# temp_press_v2.net
KiCad netlist of a schematic drawn in EAGLE
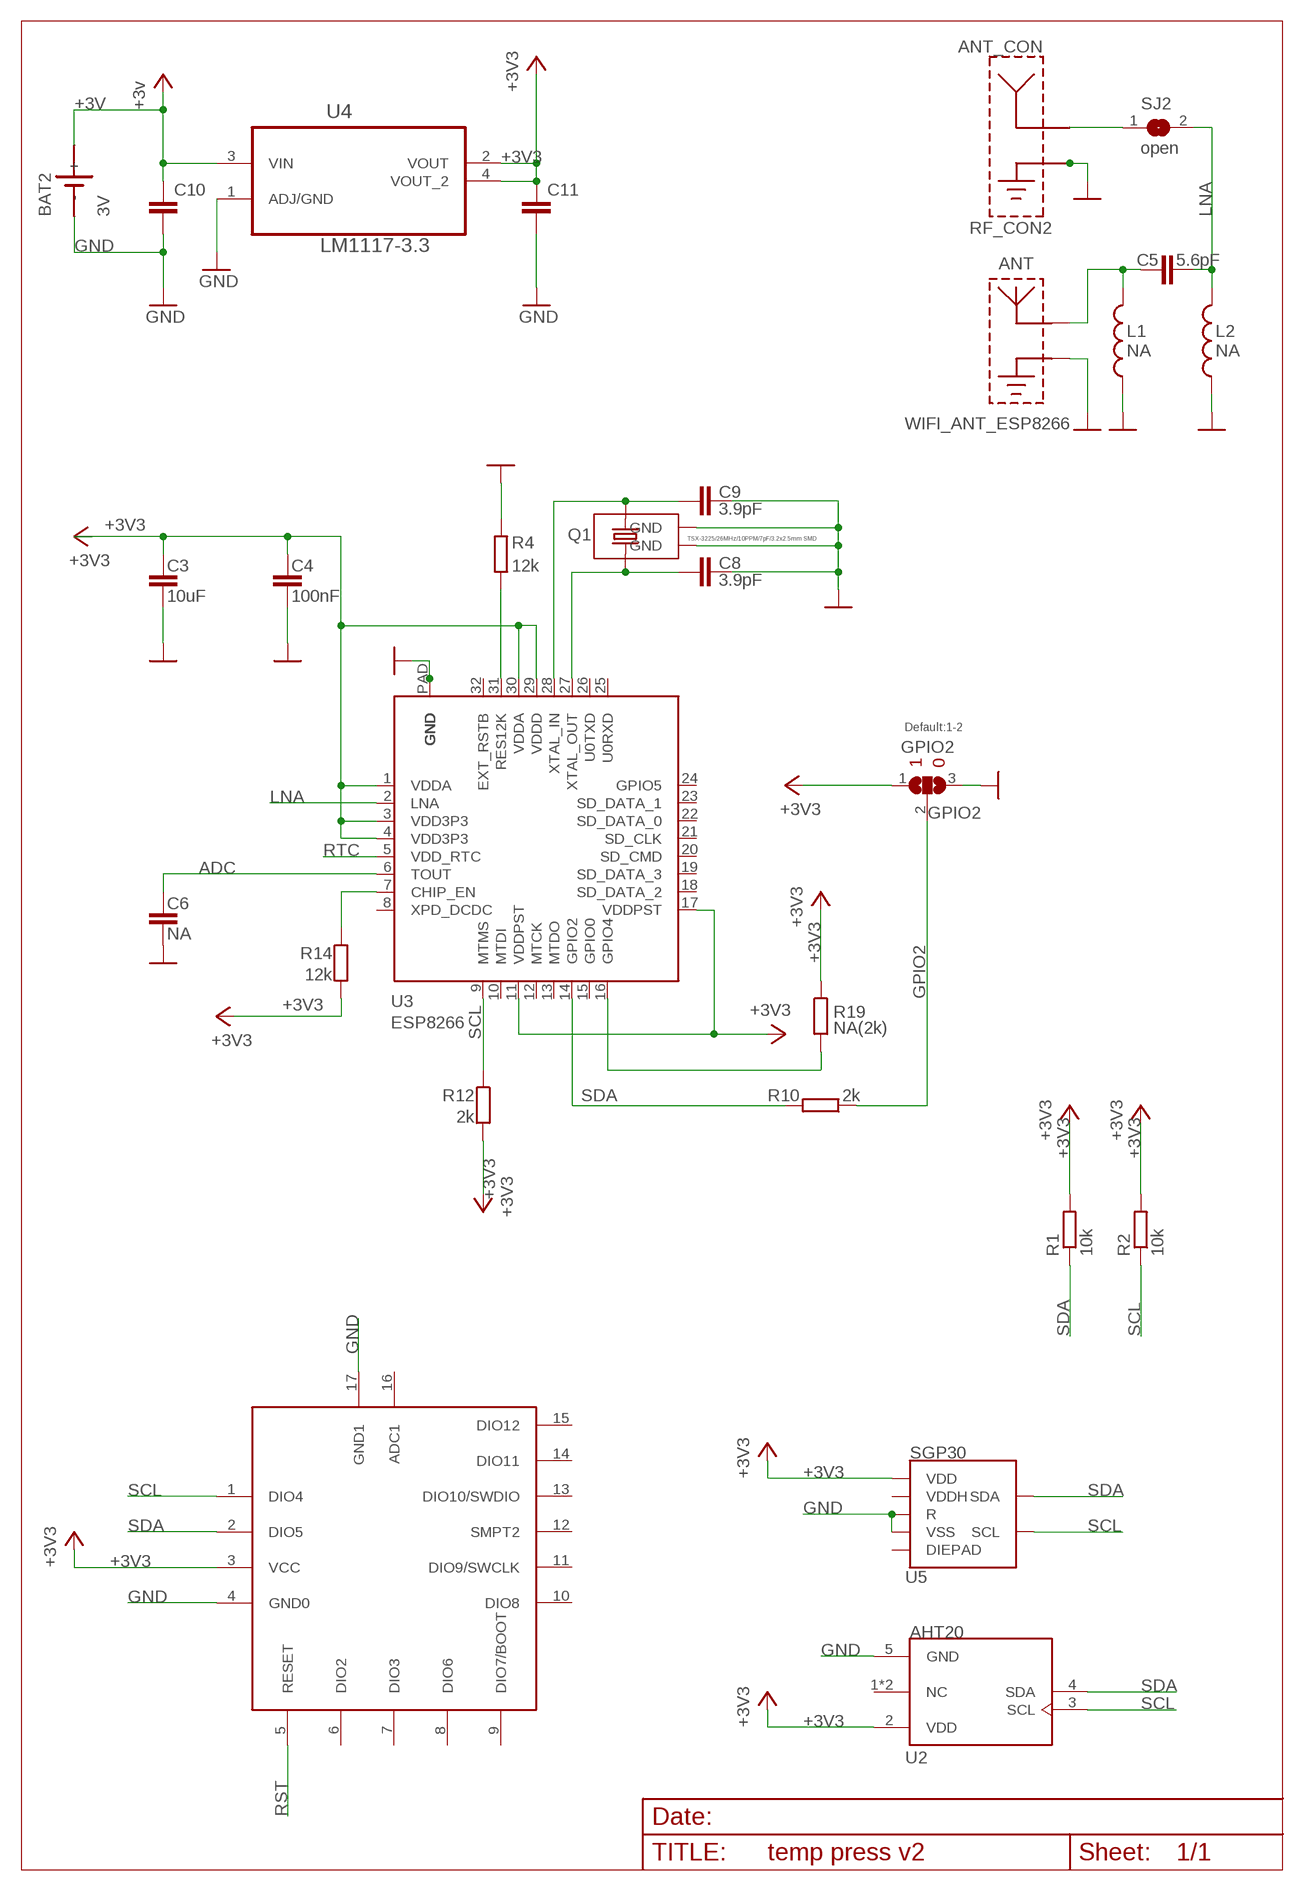
[diagram p0: schematic, sheet 1]

(export (version "E")
  (design (tool "Eeschema 10.0.6"))
  (components
    (comp (ref "ANT")
      (value "WIFI_ANT_ESP8266")
      (footprint "eagle-import:ESP8266_ANT")
      (libsource (lib "eagle-import") (part "WIFI_ANT_ESP8266"))
    )
    (comp (ref "ANT_CON")
      (value "RF_CON2")
      (footprint "eagle-import:RF_CONNECTOR_I-PEX_NO_CREAM")
      (libsource (lib "eagle-import") (part "RF_CON2"))
    )
    (comp (ref "BAT2")
      (value "3V")
      (footprint "eagle-import:SN2032")
      (libsource (lib "eagle-import") (part "SN2032"))
    )
    (comp (ref "C3")
      (value "10uF")
      (footprint "eagle-import:C0603_DWS")
      (libsource (lib "eagle-import") (part "C-EUC0603_DWS"))
    )
    (comp (ref "C4")
      (value "100nF")
      (footprint "eagle-import:C0402_TI")
      (libsource (lib "eagle-import") (part "C-EUC0402_TI"))
    )
    (comp (ref "C5")
      (value "5.6pF")
      (footprint "eagle-import:C0402_TI")
      (libsource (lib "eagle-import") (part "C-EUC0402_TI"))
    )
    (comp (ref "C6")
      (value "NA")
      (footprint "eagle-import:C0402_TI")
      (libsource (lib "eagle-import") (part "C-EUC0402_TI"))
    )
    (comp (ref "C8")
      (value "3.9pF")
      (footprint "eagle-import:C0402_TI")
      (libsource (lib "eagle-import") (part "C-EUC0402_TI"))
    )
    (comp (ref "C9")
      (value "3.9pF")
      (footprint "eagle-import:C0402_TI")
      (libsource (lib "eagle-import") (part "C-EUC0402_TI"))
    )
    (comp (ref "C10")
      (value "47u")
      (footprint "eagle-import:C1206")
      (libsource (lib "eagle-import") (part "rcl_334_C-EUC1206"))
    )
    (comp (ref "C11")
      (value "10u")
      (footprint "eagle-import:C1206")
      (libsource (lib "eagle-import") (part "rcl_334_C-EUC1206"))
    )
    (comp (ref "GPIO2")
      (value "Default:1-2")
      (footprint "eagle-import:SJ_2_SMALLER")
      (libsource (lib "eagle-import") (part "SJ2W4"))
    )
    (comp (ref "L1")
      (value "NA")
      (footprint "eagle-import:L0402_TI")
      (libsource (lib "eagle-import") (part "L-USL0402_TI"))
    )
    (comp (ref "L2")
      (value "NA")
      (footprint "eagle-import:L0402_TI")
      (libsource (lib "eagle-import") (part "L-USL0402_TI"))
    )
    (comp (ref "Q1")
      (value "TSX-3225/26MHz/10PPM/7pF/3.2x2.5mm SMD")
      (footprint "eagle-import:NX3225SA")
      (libsource (lib "eagle-import") (part "SMALL_SMD_CRYSTAL_1"))
    )
    (comp (ref "R1")
      (value "10k")
      (footprint "eagle-import:R0402")
      (libsource (lib "eagle-import") (part "rcl_334_R-EU_R0402"))
    )
    (comp (ref "R2")
      (value "10k")
      (footprint "eagle-import:R0402")
      (libsource (lib "eagle-import") (part "rcl_334_R-EU_R0402"))
    )
    (comp (ref "R4")
      (value "12k")
      (footprint "eagle-import:R0402_TI")
      (libsource (lib "eagle-import") (part "R-EU_R0402_TI"))
    )
    (comp (ref "R10")
      (value "2k")
      (footprint "eagle-import:R0402_TI")
      (libsource (lib "eagle-import") (part "R-EU_R0402_TI"))
    )
    (comp (ref "R12")
      (value "2k")
      (footprint "eagle-import:R0402_TI")
      (libsource (lib "eagle-import") (part "R-EU_R0402_TI"))
    )
    (comp (ref "R14")
      (value "12k")
      (footprint "eagle-import:R0402_TI")
      (libsource (lib "eagle-import") (part "R-EU_R0402_TI"))
    )
    (comp (ref "R19")
      (value "NA(2k)")
      (footprint "eagle-import:R0402_TI")
      (libsource (lib "eagle-import") (part "R-EU_R0402_TI"))
    )
    (comp (ref "SJ2")
      (value "open")
      (footprint "eagle-import:SJ_1_SMALLER")
      (libsource (lib "eagle-import") (part "SJSJ_SMALLER"))
    )
    (comp (ref "U$1")
      (value "BLUENRG-234BLEMODULE")
      (footprint "eagle-import:BLUENRG-234BLEMODULE")
      (libsource (lib "eagle-import") (part "BLUENRG-234BLEMODULE"))
    )
    (comp (ref "U2")
      (value "AHT20")
      (footprint "eagle-import:PSON100P300X300X110-6N")
      (fields (field (name "MF") "Asair"))
      (libsource (lib "eagle-import") (part "AHT20"))
    )
    (comp (ref "U3")
      (value "ESP8266")
      (footprint "eagle-import:QFN32_PAD")
      (libsource (lib "eagle-import") (part "ESP8266"))
    )
    (comp (ref "U4")
      (value "LM1117-3.3")
      (footprint "eagle-import:SOT230")
      (fields (field (name "MF") "Texas Instruments"))
      (libsource (lib "eagle-import") (part "LM1117-3.3"))
    )
    (comp (ref "U5")
      (value "SGP30")
      (footprint "eagle-import:SGP30")
      (fields (field (name "MF") "Sensirion AG"))
      (libsource (lib "eagle-import") (part "SGP30"))
    )
  )
  (nets
    (net (code "1") (name "+3V3") (class "Default")
      (node (ref "C11") (pin "1") (pinfunction "1_1") (pintype "passive"))
      (node (ref "C3") (pin "1") (pinfunction "1_1") (pintype "passive"))
      (node (ref "C4") (pin "1") (pinfunction "1_1") (pintype "passive"))
      (node (ref "GPIO2") (pin "1") (pinfunction "1_1") (pintype "passive"))
      (node (ref "R1") (pin "2") (pinfunction "2_2") (pintype "passive"))
      (node (ref "R12") (pin "2") (pinfunction "2_2") (pintype "passive"))
      (node (ref "R14") (pin "2") (pinfunction "2_2") (pintype "passive"))
      (node (ref "R19") (pin "1") (pinfunction "1_1") (pintype "passive"))
      (node (ref "R2") (pin "2") (pinfunction "2_2") (pintype "passive"))
      (node (ref "U$1") (pin "3") (pinfunction "VCC_3") (pintype "bidirectional"))
      (node (ref "U2") (pin "2") (pinfunction "VDD_2") (pintype "power_in"))
      (node (ref "U3") (pin "1") (pinfunction "VDDA_1") (pintype "bidirectional"))
      (node (ref "U3") (pin "11") (pinfunction "VDDPST_11") (pintype "bidirectional"))
      (node (ref "U3") (pin "17") (pinfunction "VDDPST_17") (pintype "bidirectional"))
      (node (ref "U3") (pin "29") (pinfunction "VDDD_29") (pintype "bidirectional"))
      (node (ref "U3") (pin "3") (pinfunction "VDD3P3_3") (pintype "bidirectional"))
      (node (ref "U3") (pin "30") (pinfunction "VDDA_30") (pintype "bidirectional"))
      (node (ref "U3") (pin "4") (pinfunction "VDD3P3_4") (pintype "bidirectional"))
      (node (ref "U4") (pin "2") (pinfunction "VOUT_2") (pintype "output"))
      (node (ref "U4") (pin "4") (pinfunction "VOUT_2_4") (pintype "output"))
      (node (ref "U5") (pin "1") (pinfunction "VDD_1") (pintype "bidirectional"))
    )
    (net (code "2") (name "+3v") (class "Default")
      (node (ref "BAT2") (pin "+") (pinfunction "+_+") (pintype "passive"))
      (node (ref "C10") (pin "1") (pinfunction "1_1") (pintype "passive"))
      (node (ref "U4") (pin "3") (pinfunction "VIN_3") (pintype "input"))
    )
    (net (code "3") (name "/ADC") (class "Default")
      (node (ref "C6") (pin "1") (pinfunction "1_1") (pintype "passive"))
      (node (ref "U3") (pin "6") (pinfunction "TOUT_6") (pintype "bidirectional"))
    )
    (net (code "4") (name "/GPIO2") (class "Default")
      (node (ref "GPIO2") (pin "2") (pinfunction "2_2") (pintype "passive"))
      (node (ref "R10") (pin "1") (pinfunction "1_1") (pintype "passive"))
    )
    (net (code "5") (name "/LNA") (class "Default")
      (node (ref "C5") (pin "2") (pinfunction "2_2") (pintype "passive"))
      (node (ref "L2") (pin "2") (pinfunction "2_2") (pintype "passive"))
      (node (ref "SJ2") (pin "2") (pinfunction "2_2") (pintype "passive"))
      (node (ref "U3") (pin "2") (pinfunction "LNA_2") (pintype "bidirectional"))
    )
    (net (code "6") (name "/RST") (class "Default")
      (node (ref "U$1") (pin "5") (pinfunction "RESET_5") (pintype "bidirectional"))
    )
    (net (code "7") (name "/RTC") (class "Default")
      (node (ref "U3") (pin "5") (pinfunction "VDD_RTC_5") (pintype "bidirectional"))
    )
    (net (code "8") (name "/SCL") (class "Default")
      (node (ref "R12") (pin "1") (pinfunction "1_1") (pintype "passive"))
      (node (ref "R2") (pin "1") (pinfunction "1_1") (pintype "passive"))
      (node (ref "U$1") (pin "1") (pinfunction "DIO4_1") (pintype "bidirectional"))
      (node (ref "U2") (pin "3") (pinfunction "SCL_3") (pintype "input"))
      (node (ref "U3") (pin "9") (pinfunction "MTMS_9") (pintype "bidirectional"))
      (node (ref "U5") (pin "6") (pinfunction "SCL_6") (pintype "bidirectional"))
    )
    (net (code "9") (name "/SDA") (class "Default")
      (node (ref "R1") (pin "1") (pinfunction "1_1") (pintype "passive"))
      (node (ref "R10") (pin "2") (pinfunction "2_2") (pintype "passive"))
      (node (ref "U$1") (pin "2") (pinfunction "DIO5_2") (pintype "bidirectional"))
      (node (ref "U2") (pin "4") (pinfunction "SDA_4") (pintype "bidirectional"))
      (node (ref "U3") (pin "14") (pinfunction "GPIO2_14") (pintype "bidirectional"))
      (node (ref "U5") (pin "3") (pinfunction "SDA_3") (pintype "bidirectional"))
    )
    (net (code "10") (name "GND") (class "Default")
      (node (ref "ANT") (pin "GND") (pinfunction "GND_GND") (pintype "input"))
      (node (ref "ANT_CON") (pin "1") (pinfunction "GND_1_1") (pintype "input"))
      (node (ref "ANT_CON") (pin "2") (pinfunction "GND_2_2") (pintype "input"))
      (node (ref "BAT2") (pin "-") (pinfunction "-_-") (pintype "passive"))
      (node (ref "C10") (pin "2") (pinfunction "2_2") (pintype "passive"))
      (node (ref "C11") (pin "2") (pinfunction "2_2") (pintype "passive"))
      (node (ref "C3") (pin "2") (pinfunction "2_2") (pintype "passive"))
      (node (ref "C4") (pin "2") (pinfunction "2_2") (pintype "passive"))
      (node (ref "C6") (pin "2") (pinfunction "2_2") (pintype "passive"))
      (node (ref "C8") (pin "1") (pinfunction "1_1") (pintype "passive"))
      (node (ref "C9") (pin "1") (pinfunction "1_1") (pintype "passive"))
      (node (ref "GPIO2") (pin "3") (pinfunction "3_3") (pintype "passive"))
      (node (ref "L1") (pin "1") (pinfunction "1_1") (pintype "passive"))
      (node (ref "L2") (pin "1") (pinfunction "1_1") (pintype "passive"))
      (node (ref "Q1") (pin "NC_1") (pinfunction "GND_NC_1") (pintype "power_in"))
      (node (ref "Q1") (pin "NC_2") (pinfunction "GND_NC_2") (pintype "power_in"))
      (node (ref "R4") (pin "2") (pinfunction "2_2") (pintype "passive"))
      (node (ref "U$1") (pin "17") (pinfunction "GND1_17") (pintype "bidirectional"))
      (node (ref "U$1") (pin "4") (pinfunction "GND0_4") (pintype "bidirectional"))
      (node (ref "U2") (pin "5") (pinfunction "GND_5") (pintype "power_in"))
      (node (ref "U3") (pin "P$1") (pinfunction "GND_P$1") (pintype "bidirectional"))
      (node (ref "U3") (pin "P$2") (pinfunction "GND_P$2") (pintype "bidirectional"))
      (node (ref "U3") (pin "P$3") (pinfunction "GND_P$3") (pintype "bidirectional"))
      (node (ref "U3") (pin "P$4") (pinfunction "GND_P$4") (pintype "bidirectional"))
      (node (ref "U3") (pin "P$5") (pinfunction "GND_P$5") (pintype "bidirectional"))
      (node (ref "U3") (pin "P$6") (pinfunction "GND_P$6") (pintype "bidirectional"))
      (node (ref "U3") (pin "P$7") (pinfunction "GND_P$7") (pintype "bidirectional"))
      (node (ref "U3") (pin "P$8") (pinfunction "GND_P$8") (pintype "bidirectional"))
      (node (ref "U3") (pin "P$9") (pinfunction "GND_P$9") (pintype "bidirectional"))
      (node (ref "U3") (pin "PAD") (pinfunction "GND_PAD") (pintype "bidirectional"))
      (node (ref "U4") (pin "1") (pinfunction "ADJ/GND_1") (pintype "passive"))
      (node (ref "U5") (pin "2") (pinfunction "VSS_2") (pintype "bidirectional"))
      (node (ref "U5") (pin "4") (pinfunction "R_4") (pintype "bidirectional"))
    )
    (net (code "11") (name "Net-(ANT-PadANT)") (class "Default")
      (node (ref "ANT") (pin "ANT") (pinfunction "ANT_ANT") (pintype "input"))
      (node (ref "C5") (pin "1") (pinfunction "1_1") (pintype "passive"))
      (node (ref "L1") (pin "2") (pinfunction "2_2") (pintype "passive"))
    )
    (net (code "12") (name "Net-(ANT_CON-PadANT)") (class "Default")
      (node (ref "ANT_CON") (pin "ANT") (pinfunction "ANT_ANT") (pintype "power_in"))
      (node (ref "SJ2") (pin "1") (pinfunction "1_1") (pintype "passive"))
    )
    (net (code "13") (name "Net-(U3-CHIP_EN)") (class "Default")
      (node (ref "R14") (pin "1") (pinfunction "1_1") (pintype "passive"))
      (node (ref "U3") (pin "7") (pinfunction "CHIP_EN_7") (pintype "bidirectional"))
    )
    (net (code "14") (name "Net-(U3-GPIO4)") (class "Default")
      (node (ref "R19") (pin "2") (pinfunction "2_2") (pintype "passive"))
      (node (ref "U3") (pin "16") (pinfunction "GPIO4_16") (pintype "bidirectional"))
    )
    (net (code "15") (name "Net-(U3-RES12K)") (class "Default")
      (node (ref "R4") (pin "1") (pinfunction "1_1") (pintype "passive"))
      (node (ref "U3") (pin "31") (pinfunction "RES12K_31") (pintype "bidirectional"))
    )
    (net (code "16") (name "Net-(U3-XTAL_IN)") (class "Default")
      (node (ref "C9") (pin "2") (pinfunction "2_2") (pintype "passive"))
      (node (ref "Q1") (pin "1") (pinfunction "1_1") (pintype "input"))
      (node (ref "U3") (pin "28") (pinfunction "XTAL_IN_28") (pintype "bidirectional"))
    )
    (net (code "17") (name "Net-(U3-XTAL_OUT)") (class "Default")
      (node (ref "C8") (pin "2") (pinfunction "2_2") (pintype "passive"))
      (node (ref "Q1") (pin "2") (pinfunction "2_2") (pintype "input"))
      (node (ref "U3") (pin "27") (pinfunction "XTAL_OUT_27") (pintype "bidirectional"))
    )
    (net (code "18") (name "unconnected-(U$1-ADC1-Pad16)") (class "Default")
      (node (ref "U$1") (pin "16") (pinfunction "ADC1_16") (pintype "bidirectional"))
    )
    (net (code "19") (name "unconnected-(U$1-DIO2-Pad6)") (class "Default")
      (node (ref "U$1") (pin "6") (pinfunction "DIO2_6") (pintype "bidirectional"))
    )
    (net (code "20") (name "unconnected-(U$1-DIO3-Pad7)") (class "Default")
      (node (ref "U$1") (pin "7") (pinfunction "DIO3_7") (pintype "bidirectional"))
    )
    (net (code "21") (name "unconnected-(U$1-DIO6-Pad8)") (class "Default")
      (node (ref "U$1") (pin "8") (pinfunction "DIO6_8") (pintype "bidirectional"))
    )
    (net (code "22") (name "unconnected-(U$1-DIO7{slash}BOOT-Pad9)") (class "Default")
      (node (ref "U$1") (pin "9") (pinfunction "DIO7/BOOT_9") (pintype "bidirectional"))
    )
    (net (code "23") (name "unconnected-(U$1-DIO8-Pad10)") (class "Default")
      (node (ref "U$1") (pin "10") (pinfunction "DIO8_10") (pintype "bidirectional"))
    )
    (net (code "24") (name "unconnected-(U$1-DIO9{slash}SWCLK-Pad11)") (class "Default")
      (node (ref "U$1") (pin "11") (pinfunction "DIO9/SWCLK_11") (pintype "bidirectional"))
    )
    (net (code "25") (name "unconnected-(U$1-DIO10{slash}SWDIO-Pad13)") (class "Default")
      (node (ref "U$1") (pin "13") (pinfunction "DIO10/SWDIO_13") (pintype "bidirectional"))
    )
    (net (code "26") (name "unconnected-(U$1-DIO11-Pad14)") (class "Default")
      (node (ref "U$1") (pin "14") (pinfunction "DIO11_14") (pintype "bidirectional"))
    )
    (net (code "27") (name "unconnected-(U$1-DIO12-Pad15)") (class "Default")
      (node (ref "U$1") (pin "15") (pinfunction "DIO12_15") (pintype "bidirectional"))
    )
    (net (code "28") (name "unconnected-(U$1-SMPT2-Pad12)") (class "Default")
      (node (ref "U$1") (pin "12") (pinfunction "SMPT2_12") (pintype "bidirectional"))
    )
    (net (code "29") (name "unconnected-(U2-NC-Pad1)") (class "Default")
      (node (ref "U2") (pin "1") (pinfunction "NC_1") (pintype "no_connect"))
    )
    (net (code "30") (name "unconnected-(U2-NC-Pad6)") (class "Default")
      (node (ref "U2") (pin "6") (pinfunction "NC_6") (pintype "no_connect"))
    )
    (net (code "31") (name "unconnected-(U3-EXT_RSTB-Pad32)") (class "Default")
      (node (ref "U3") (pin "32") (pinfunction "EXT_RSTB_32") (pintype "bidirectional"))
    )
    (net (code "32") (name "unconnected-(U3-GPIO0-Pad15)") (class "Default")
      (node (ref "U3") (pin "15") (pinfunction "GPIO0_15") (pintype "bidirectional"))
    )
    (net (code "33") (name "unconnected-(U3-GPIO5-Pad24)") (class "Default")
      (node (ref "U3") (pin "24") (pinfunction "GPIO5_24") (pintype "bidirectional"))
    )
    (net (code "34") (name "unconnected-(U3-MTCK-Pad12)") (class "Default")
      (node (ref "U3") (pin "12") (pinfunction "MTCK_12") (pintype "bidirectional"))
    )
    (net (code "35") (name "unconnected-(U3-MTDI-Pad10)") (class "Default")
      (node (ref "U3") (pin "10") (pinfunction "MTDI_10") (pintype "bidirectional"))
    )
    (net (code "36") (name "unconnected-(U3-MTDO-Pad13)") (class "Default")
      (node (ref "U3") (pin "13") (pinfunction "MTDO_13") (pintype "bidirectional"))
    )
    (net (code "37") (name "unconnected-(U3-SD_CLK-Pad21)") (class "Default")
      (node (ref "U3") (pin "21") (pinfunction "SD_CLK_21") (pintype "bidirectional"))
    )
    (net (code "38") (name "unconnected-(U3-SD_CMD-Pad20)") (class "Default")
      (node (ref "U3") (pin "20") (pinfunction "SD_CMD_20") (pintype "bidirectional"))
    )
    (net (code "39") (name "unconnected-(U3-SD_DATA_0-Pad22)") (class "Default")
      (node (ref "U3") (pin "22") (pinfunction "SD_DATA_0_22") (pintype "bidirectional"))
    )
    (net (code "40") (name "unconnected-(U3-SD_DATA_1-Pad23)") (class "Default")
      (node (ref "U3") (pin "23") (pinfunction "SD_DATA_1_23") (pintype "bidirectional"))
    )
    (net (code "41") (name "unconnected-(U3-SD_DATA_2-Pad18)") (class "Default")
      (node (ref "U3") (pin "18") (pinfunction "SD_DATA_2_18") (pintype "bidirectional"))
    )
    (net (code "42") (name "unconnected-(U3-SD_DATA_3-Pad19)") (class "Default")
      (node (ref "U3") (pin "19") (pinfunction "SD_DATA_3_19") (pintype "bidirectional"))
    )
    (net (code "43") (name "unconnected-(U3-U0RXD-Pad25)") (class "Default")
      (node (ref "U3") (pin "25") (pinfunction "U0RXD_25") (pintype "bidirectional"))
    )
    (net (code "44") (name "unconnected-(U3-U0TXD-Pad26)") (class "Default")
      (node (ref "U3") (pin "26") (pinfunction "U0TXD_26") (pintype "bidirectional"))
    )
    (net (code "45") (name "unconnected-(U3-XPD_DCDC-Pad8)") (class "Default")
      (node (ref "U3") (pin "8") (pinfunction "XPD_DCDC_8") (pintype "bidirectional"))
    )
    (net (code "46") (name "unconnected-(U5-PadDIEPAD)") (class "Default")
      (node (ref "U5") (pin "DIEPAD") (pinfunction "DIEPAD_DIEPAD") (pintype "bidirectional"))
    )
    (net (code "47") (name "unconnected-(U5-VDDH-Pad5)") (class "Default")
      (node (ref "U5") (pin "5") (pinfunction "VDDH_5") (pintype "bidirectional"))
    )
  )
)
